# adaptador_scart_v1.net
KiCad netlist of a schematic drawn in EAGLE
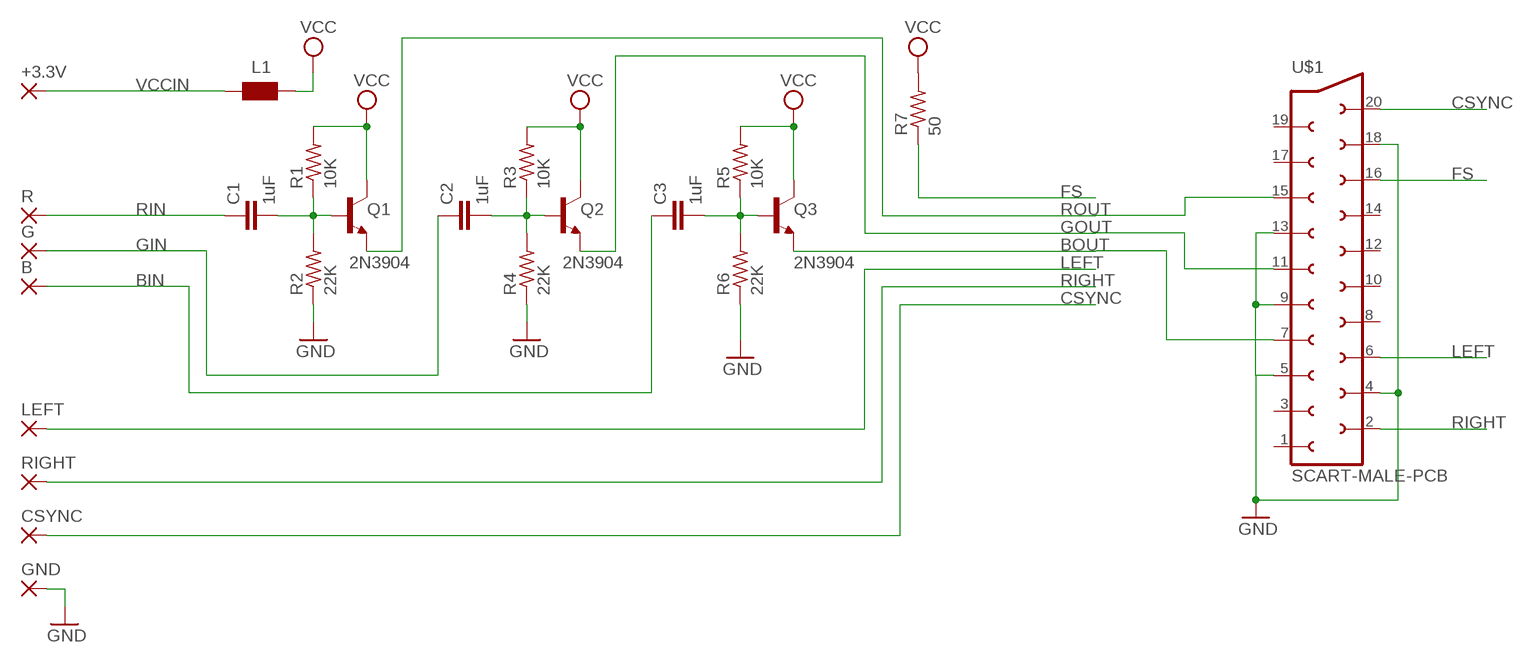
[diagram p0: schematic, sheet 1]

(export (version "E")
  (design (tool "Eeschema 10.0.6"))
  (components
    (comp (ref "+3.3V")
      (value "SMD2")
      (footprint "eagle-import:SMD1,27-2,54")
      (libsource (lib "eagle-import") (part "SMD2"))
    )
    (comp (ref "B")
      (value "SMD2")
      (footprint "eagle-import:SMD1,27-2,54")
      (libsource (lib "eagle-import") (part "SMD2"))
    )
    (comp (ref "C1")
      (value "1uF")
      (footprint "eagle-import:C1206K")
      (libsource (lib "eagle-import") (part "C-EUC1206K"))
    )
    (comp (ref "C2")
      (value "1uF")
      (footprint "eagle-import:C1206K")
      (libsource (lib "eagle-import") (part "C-EUC1206K"))
    )
    (comp (ref "C3")
      (value "1uF")
      (footprint "eagle-import:C1206K")
      (libsource (lib "eagle-import") (part "C-EUC1206K"))
    )
    (comp (ref "CSYNC")
      (value "SMD2")
      (footprint "eagle-import:SMD1,27-2,54")
      (libsource (lib "eagle-import") (part "SMD2"))
    )
    (comp (ref "G")
      (value "SMD2")
      (footprint "eagle-import:SMD1,27-2,54")
      (libsource (lib "eagle-import") (part "SMD2"))
    )
    (comp (ref "GND")
      (value "SMD2")
      (footprint "eagle-import:SMD1,27-2,54")
      (libsource (lib "eagle-import") (part "SMD2"))
    )
    (comp (ref "L1")
      (value "WE-CBF_0805")
      (footprint "eagle-import:0805")
      (libsource (lib "eagle-import") (part "WE-CBF_0805"))
    )
    (comp (ref "LEFT")
      (value "SMD2")
      (footprint "eagle-import:SMD1,27-2,54")
      (libsource (lib "eagle-import") (part "SMD2"))
    )
    (comp (ref "Q1")
      (value "2N3904")
      (footprint "eagle-import:SOT23")
      (libsource (lib "eagle-import") (part "BC847SMDC"))
    )
    (comp (ref "Q2")
      (value "2N3904")
      (footprint "eagle-import:SOT23")
      (libsource (lib "eagle-import") (part "BC847SMDC"))
    )
    (comp (ref "Q3")
      (value "2N3904")
      (footprint "eagle-import:SOT23")
      (libsource (lib "eagle-import") (part "BC847SMDC"))
    )
    (comp (ref "R")
      (value "SMD2")
      (footprint "eagle-import:SMD1,27-2,54")
      (libsource (lib "eagle-import") (part "SMD2"))
    )
    (comp (ref "R1")
      (value "10K")
      (footprint "eagle-import:R0805")
      (libsource (lib "eagle-import") (part "R-US_R0805"))
    )
    (comp (ref "R2")
      (value "22K")
      (footprint "eagle-import:R0805")
      (libsource (lib "eagle-import") (part "R-US_R0805"))
    )
    (comp (ref "R3")
      (value "10K")
      (footprint "eagle-import:R0805")
      (libsource (lib "eagle-import") (part "R-US_R0805"))
    )
    (comp (ref "R4")
      (value "22K")
      (footprint "eagle-import:R0805")
      (libsource (lib "eagle-import") (part "R-US_R0805"))
    )
    (comp (ref "R5")
      (value "10K")
      (footprint "eagle-import:R0805")
      (libsource (lib "eagle-import") (part "R-US_R0805"))
    )
    (comp (ref "R6")
      (value "22K")
      (footprint "eagle-import:R0805")
      (libsource (lib "eagle-import") (part "R-US_R0805"))
    )
    (comp (ref "R7")
      (value "50")
      (footprint "eagle-import:R0805")
      (libsource (lib "eagle-import") (part "R-US_R0805"))
    )
    (comp (ref "RIGHT")
      (value "SMD2")
      (footprint "eagle-import:SMD1,27-2,54")
      (libsource (lib "eagle-import") (part "SMD2"))
    )
    (comp (ref "U$1")
      (value "SCART-MALE-PCB")
      (footprint "eagle-import:SCART-PCB")
      (libsource (lib "eagle-import") (part "SCART-MALE-PCB"))
    )
  )
  (nets
    (net (code "1") (name "/BIN") (class "Default")
      (node (ref "B") (pin "1") (pinfunction "P_1") (pintype "passive"))
      (node (ref "C3") (pin "1") (pinfunction "1_1") (pintype "passive"))
    )
    (net (code "2") (name "/BOUT") (class "Default")
      (node (ref "Q3") (pin "2") (pinfunction "E_2") (pintype "passive"))
      (node (ref "U$1") (pin "7") (pinfunction "7_7") (pintype "passive"))
    )
    (net (code "3") (name "/CSYNC") (class "Default")
      (node (ref "CSYNC") (pin "1") (pinfunction "P_1") (pintype "passive"))
      (node (ref "U$1") (pin "20") (pinfunction "20_20") (pintype "passive"))
    )
    (net (code "4") (name "/FS") (class "Default")
      (node (ref "R7") (pin "1") (pinfunction "1_1") (pintype "passive"))
      (node (ref "U$1") (pin "16") (pinfunction "16_16") (pintype "passive"))
    )
    (net (code "5") (name "/GIN") (class "Default")
      (node (ref "C2") (pin "1") (pinfunction "1_1") (pintype "passive"))
      (node (ref "G") (pin "1") (pinfunction "P_1") (pintype "passive"))
    )
    (net (code "6") (name "/GOUT") (class "Default")
      (node (ref "Q2") (pin "2") (pinfunction "E_2") (pintype "passive"))
      (node (ref "U$1") (pin "11") (pinfunction "11_11") (pintype "passive"))
    )
    (net (code "7") (name "/LEFT") (class "Default")
      (node (ref "LEFT") (pin "1") (pinfunction "P_1") (pintype "passive"))
      (node (ref "U$1") (pin "6") (pinfunction "6_6") (pintype "passive"))
    )
    (net (code "8") (name "/RIGHT") (class "Default")
      (node (ref "RIGHT") (pin "1") (pinfunction "P_1") (pintype "passive"))
      (node (ref "U$1") (pin "2") (pinfunction "2_2") (pintype "passive"))
    )
    (net (code "9") (name "/RIN") (class "Default")
      (node (ref "C1") (pin "1") (pinfunction "1_1") (pintype "passive"))
      (node (ref "R") (pin "1") (pinfunction "P_1") (pintype "passive"))
    )
    (net (code "10") (name "/ROUT") (class "Default")
      (node (ref "Q1") (pin "2") (pinfunction "E_2") (pintype "passive"))
      (node (ref "U$1") (pin "15") (pinfunction "15_15") (pintype "passive"))
    )
    (net (code "11") (name "/VCCIN") (class "Default")
      (node (ref "+3.3V") (pin "1") (pinfunction "P_1") (pintype "passive"))
      (node (ref "L1") (pin "1") (pinfunction "1_1") (pintype "passive"))
    )
    (net (code "12") (name "GND") (class "Default")
      (node (ref "GND") (pin "1") (pinfunction "P_1") (pintype "passive"))
      (node (ref "R2") (pin "1") (pinfunction "1_1") (pintype "passive"))
      (node (ref "R4") (pin "1") (pinfunction "1_1") (pintype "passive"))
      (node (ref "R6") (pin "1") (pinfunction "1_1") (pintype "passive"))
      (node (ref "U$1") (pin "13") (pinfunction "13_13") (pintype "passive"))
      (node (ref "U$1") (pin "18") (pinfunction "18_18") (pintype "passive"))
      (node (ref "U$1") (pin "4") (pinfunction "4_4") (pintype "passive"))
      (node (ref "U$1") (pin "5") (pinfunction "5_5") (pintype "passive"))
      (node (ref "U$1") (pin "9") (pinfunction "9_9") (pintype "passive"))
    )
    (net (code "13") (name "Net-(Q1-B)") (class "Default")
      (node (ref "C1") (pin "2") (pinfunction "2_2") (pintype "passive"))
      (node (ref "Q1") (pin "1") (pinfunction "B_1") (pintype "passive"))
      (node (ref "R1") (pin "1") (pinfunction "1_1") (pintype "passive"))
      (node (ref "R2") (pin "2") (pinfunction "2_2") (pintype "passive"))
    )
    (net (code "14") (name "Net-(Q2-B)") (class "Default")
      (node (ref "C2") (pin "2") (pinfunction "2_2") (pintype "passive"))
      (node (ref "Q2") (pin "1") (pinfunction "B_1") (pintype "passive"))
      (node (ref "R3") (pin "1") (pinfunction "1_1") (pintype "passive"))
      (node (ref "R4") (pin "2") (pinfunction "2_2") (pintype "passive"))
    )
    (net (code "15") (name "Net-(Q3-B)") (class "Default")
      (node (ref "C3") (pin "2") (pinfunction "2_2") (pintype "passive"))
      (node (ref "Q3") (pin "1") (pinfunction "B_1") (pintype "passive"))
      (node (ref "R5") (pin "1") (pinfunction "1_1") (pintype "passive"))
      (node (ref "R6") (pin "2") (pinfunction "2_2") (pintype "passive"))
    )
    (net (code "16") (name "VCC") (class "Default")
      (node (ref "L1") (pin "2") (pinfunction "2_2") (pintype "passive"))
      (node (ref "Q1") (pin "3") (pinfunction "C_3") (pintype "passive"))
      (node (ref "Q2") (pin "3") (pinfunction "C_3") (pintype "passive"))
      (node (ref "Q3") (pin "3") (pinfunction "C_3") (pintype "passive"))
      (node (ref "R1") (pin "2") (pinfunction "2_2") (pintype "passive"))
      (node (ref "R3") (pin "2") (pinfunction "2_2") (pintype "passive"))
      (node (ref "R5") (pin "2") (pinfunction "2_2") (pintype "passive"))
      (node (ref "R7") (pin "2") (pinfunction "2_2") (pintype "passive"))
    )
    (net (code "17") (name "unconnected-(U$1-Pad1)") (class "Default")
      (node (ref "U$1") (pin "1") (pinfunction "1_1") (pintype "passive"))
    )
    (net (code "18") (name "unconnected-(U$1-Pad3)") (class "Default")
      (node (ref "U$1") (pin "3") (pinfunction "3_3") (pintype "passive"))
    )
    (net (code "19") (name "unconnected-(U$1-Pad8)") (class "Default")
      (node (ref "U$1") (pin "8") (pinfunction "8_8") (pintype "passive"))
    )
    (net (code "20") (name "unconnected-(U$1-Pad10)") (class "Default")
      (node (ref "U$1") (pin "10") (pinfunction "10_10") (pintype "passive"))
    )
    (net (code "21") (name "unconnected-(U$1-Pad12)") (class "Default")
      (node (ref "U$1") (pin "12") (pinfunction "12_12") (pintype "passive"))
    )
    (net (code "22") (name "unconnected-(U$1-Pad14)") (class "Default")
      (node (ref "U$1") (pin "14") (pinfunction "14_14") (pintype "passive"))
    )
    (net (code "23") (name "unconnected-(U$1-Pad17)") (class "Default")
      (node (ref "U$1") (pin "17") (pinfunction "17_17") (pintype "passive"))
    )
    (net (code "24") (name "unconnected-(U$1-Pad19)") (class "Default")
      (node (ref "U$1") (pin "19") (pinfunction "19_19") (pintype "passive"))
    )
  )
)
